# Tally_Box_With_Ethernet.net
KiCad netlist of a schematic drawn in EAGLE
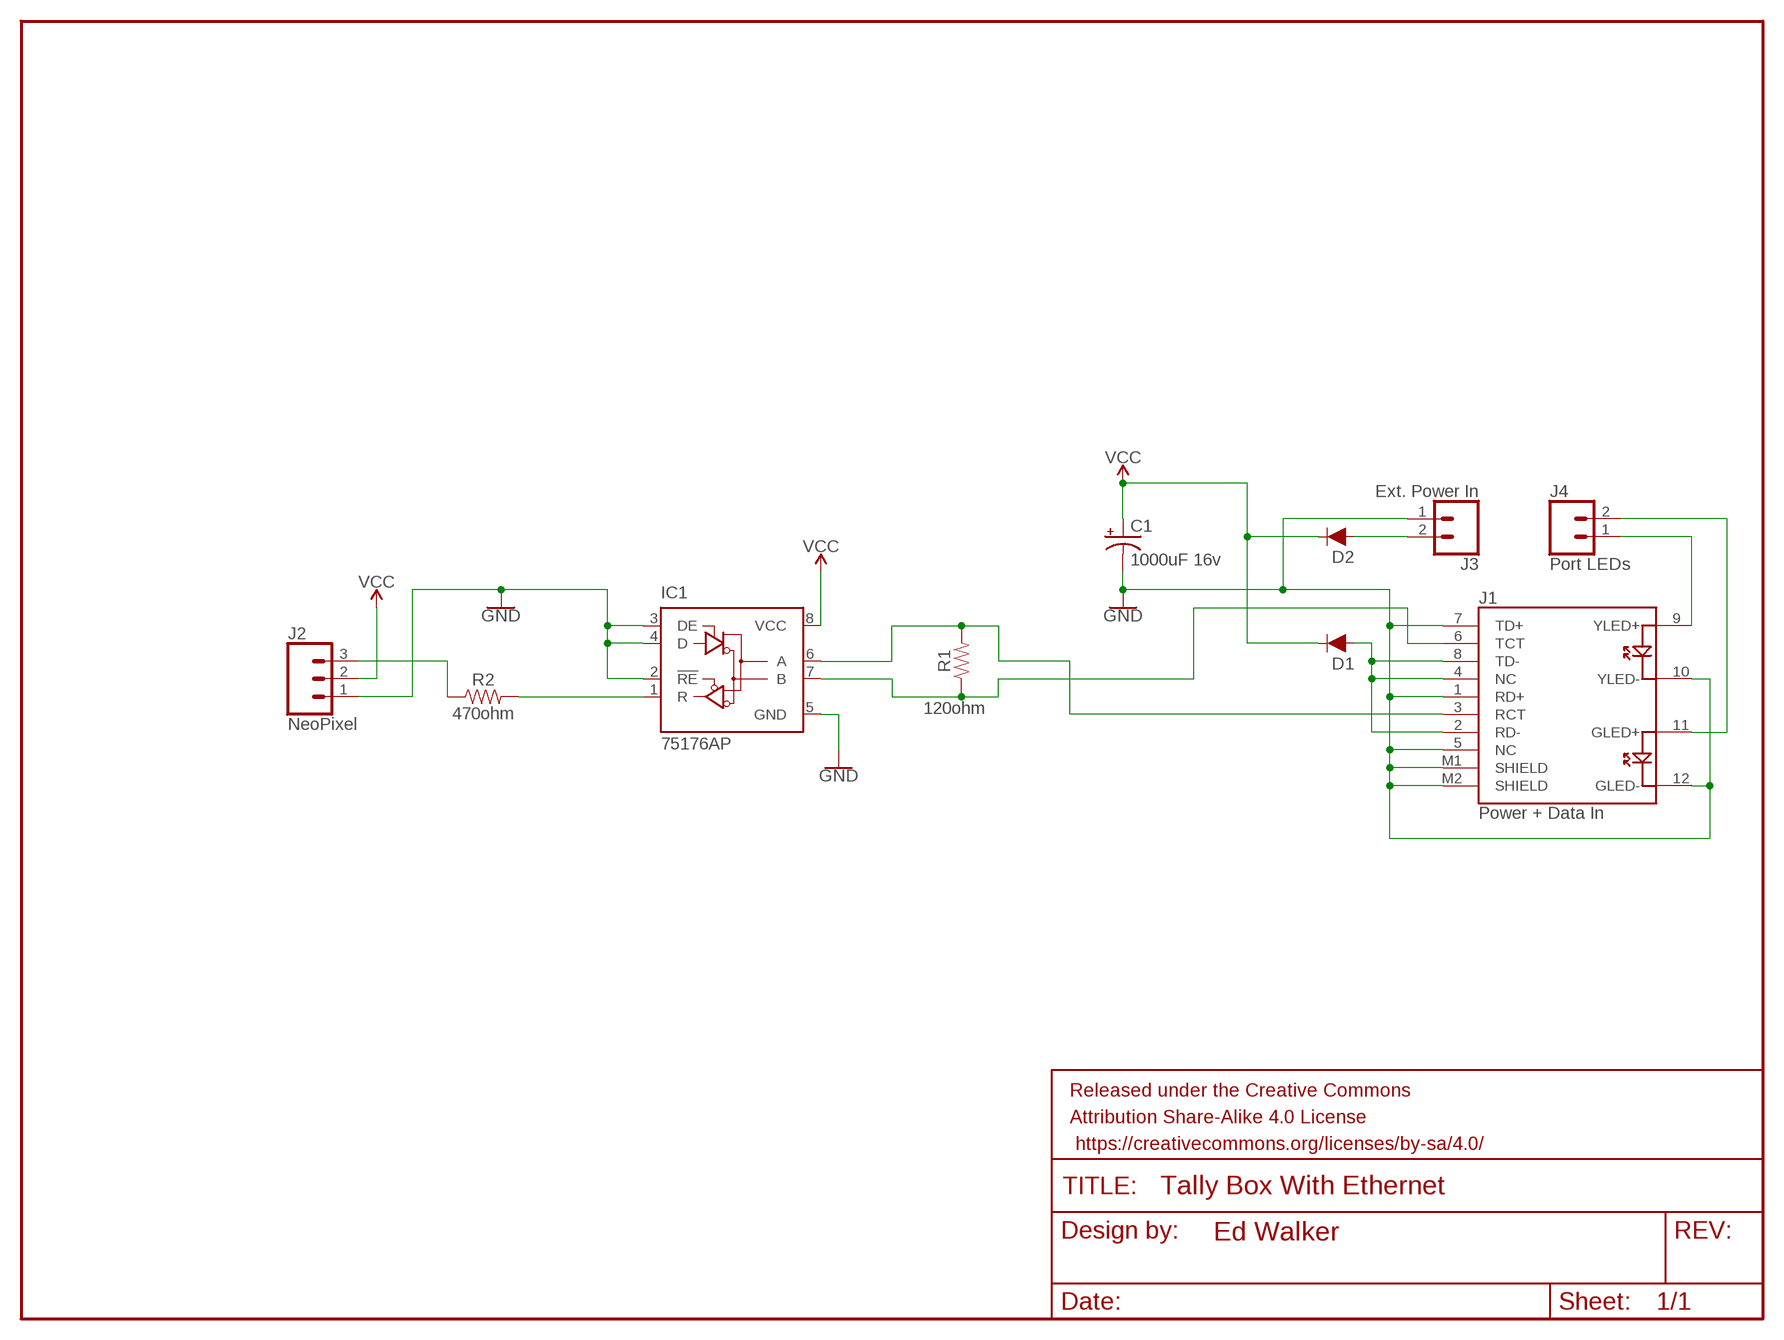
[diagram p0: schematic, sheet 1]

(export (version "E")
  (design (tool "Eeschema 10.0.6"))
  (components
    (comp (ref "C1")
      (value "1000uF 16v")
      (footprint "eagle-import:CPOL-RADIAL-5MM-10MM")
      (libsource (lib "eagle-import") (part "1000UF-RADIAL-5MM-25V-20%"))
    )
    (comp (ref "D1")
      (value "DIODE-PTH")
      (footprint "eagle-import:DIODE-1N4001")
      (libsource (lib "eagle-import") (part "DIODE-PTH"))
    )
    (comp (ref "D2")
      (value "DIODE-PTH")
      (footprint "eagle-import:DIODE-1N4001")
      (libsource (lib "eagle-import") (part "DIODE-PTH"))
    )
    (comp (ref "FRAME1")
      (value "FRAME-LETTERNO_PACKAGE")
      (footprint "eagle-import:DUMMY")
      (fields (field (name "DESIGNER") "Ed Walker") (field (name "DESIGNER_1") "Ed Walker"))
      (libsource (lib "eagle-import") (part "FRAME-LETTERNO_PACKAGE"))
    )
    (comp (ref "IC1")
      (value "75176AP")
      (footprint "eagle-import:DIL08")
      (libsource (lib "eagle-import") (part "75176AP"))
    )
    (comp (ref "J1")
      (value "Power + Data In")
      (footprint "eagle-import:MAGJACK")
      (libsource (lib "eagle-import") (part "MAGJACK"))
    )
    (comp (ref "J2")
      (value "NeoPixel")
      (footprint "eagle-import:1X03")
      (libsource (lib "eagle-import") (part "CONN_03"))
    )
    (comp (ref "J3")
      (value "Ext. Power In")
      (footprint "eagle-import:1X02")
      (libsource (lib "eagle-import") (part "CONN_02"))
    )
    (comp (ref "J4")
      (value "Port LEDs")
      (footprint "eagle-import:1X02")
      (libsource (lib "eagle-import") (part "CONN_02"))
    )
    (comp (ref "R1")
      (value "120ohm")
      (footprint "eagle-import:AXIAL-0.3")
      (libsource (lib "eagle-import") (part "RESISTORAXIAL-0.3"))
    )
    (comp (ref "R2")
      (value "470ohm")
      (footprint "eagle-import:AXIAL-0.3")
      (libsource (lib "eagle-import") (part "RESISTORAXIAL-0.3"))
    )
  )
  (nets
    (net (code "1") (name "GND") (class "Default")
      (node (ref "C1") (pin "-") (pinfunction "-_-") (pintype "passive"))
      (node (ref "IC1") (pin "2") (pinfunction "~{RE}_2") (pintype "input"))
      (node (ref "IC1") (pin "3") (pinfunction "DE_3") (pintype "input"))
      (node (ref "IC1") (pin "4") (pinfunction "D_4") (pintype "input"))
      (node (ref "IC1") (pin "5") (pinfunction "GND_5") (pintype "power_in"))
      (node (ref "J1") (pin "1") (pinfunction "RD+_1") (pintype "bidirectional"))
      (node (ref "J1") (pin "10") (pinfunction "YLED-_10") (pintype "bidirectional"))
      (node (ref "J1") (pin "12") (pinfunction "GLED-_12") (pintype "bidirectional"))
      (node (ref "J1") (pin "5") (pinfunction "NC_5") (pintype "bidirectional"))
      (node (ref "J1") (pin "7") (pinfunction "TD+_7") (pintype "bidirectional"))
      (node (ref "J1") (pin "M1") (pinfunction "SHIELD_M1") (pintype "bidirectional"))
      (node (ref "J1") (pin "M2") (pinfunction "SHIELD_M2") (pintype "bidirectional"))
      (node (ref "J2") (pin "1") (pinfunction "1_1") (pintype "passive"))
      (node (ref "J3") (pin "1") (pinfunction "1_1") (pintype "passive"))
    )
    (net (code "2") (name "Net-(D2-PadA)") (class "Default")
      (node (ref "D2") (pin "A") (pinfunction "A_A") (pintype "passive"))
      (node (ref "J3") (pin "2") (pinfunction "2_2") (pintype "passive"))
    )
    (net (code "3") (name "Net-(IC1-A)") (class "Default")
      (node (ref "IC1") (pin "6") (pinfunction "A_6") (pintype "output"))
      (node (ref "J1") (pin "3") (pinfunction "RCT_3") (pintype "bidirectional"))
      (node (ref "R1") (pin "P$2") (pinfunction "2_P$2") (pintype "passive"))
    )
    (net (code "4") (name "Net-(IC1-B)") (class "Default")
      (node (ref "IC1") (pin "7") (pinfunction "B_7") (pintype "output"))
      (node (ref "J1") (pin "6") (pinfunction "TCT_6") (pintype "bidirectional"))
      (node (ref "R1") (pin "P$1") (pinfunction "1_P$1") (pintype "passive"))
    )
    (net (code "5") (name "Net-(IC1-R)") (class "Default")
      (node (ref "IC1") (pin "1") (pinfunction "R_1") (pintype "input"))
      (node (ref "R2") (pin "P$2") (pinfunction "2_P$2") (pintype "passive"))
    )
    (net (code "6") (name "Net-(J1-GLED+)") (class "Default")
      (node (ref "J1") (pin "11") (pinfunction "GLED+_11") (pintype "bidirectional"))
      (node (ref "J4") (pin "2") (pinfunction "2_2") (pintype "passive"))
    )
    (net (code "7") (name "Net-(J1-RD-)") (class "Default")
      (node (ref "D1") (pin "A") (pinfunction "A_A") (pintype "passive"))
      (node (ref "J1") (pin "2") (pinfunction "RD-_2") (pintype "bidirectional"))
      (node (ref "J1") (pin "4") (pinfunction "NC_4") (pintype "bidirectional"))
      (node (ref "J1") (pin "8") (pinfunction "TD-_8") (pintype "bidirectional"))
    )
    (net (code "8") (name "Net-(J1-YLED+)") (class "Default")
      (node (ref "J1") (pin "9") (pinfunction "YLED+_9") (pintype "bidirectional"))
      (node (ref "J4") (pin "1") (pinfunction "1_1") (pintype "passive"))
    )
    (net (code "9") (name "Net-(R2-1)") (class "Default")
      (node (ref "J2") (pin "3") (pinfunction "3_3") (pintype "passive"))
      (node (ref "R2") (pin "P$1") (pinfunction "1_P$1") (pintype "passive"))
    )
    (net (code "10") (name "VCC") (class "Default")
      (node (ref "C1") (pin "+") (pinfunction "+_+") (pintype "passive"))
      (node (ref "D1") (pin "C") (pinfunction "C_C") (pintype "passive"))
      (node (ref "D2") (pin "C") (pinfunction "C_C") (pintype "passive"))
      (node (ref "IC1") (pin "8") (pinfunction "VCC_8") (pintype "power_in"))
      (node (ref "J2") (pin "2") (pinfunction "2_2") (pintype "passive"))
    )
  )
)
